# Proiect_v75.net
KiCad netlist of a schematic drawn in EAGLE
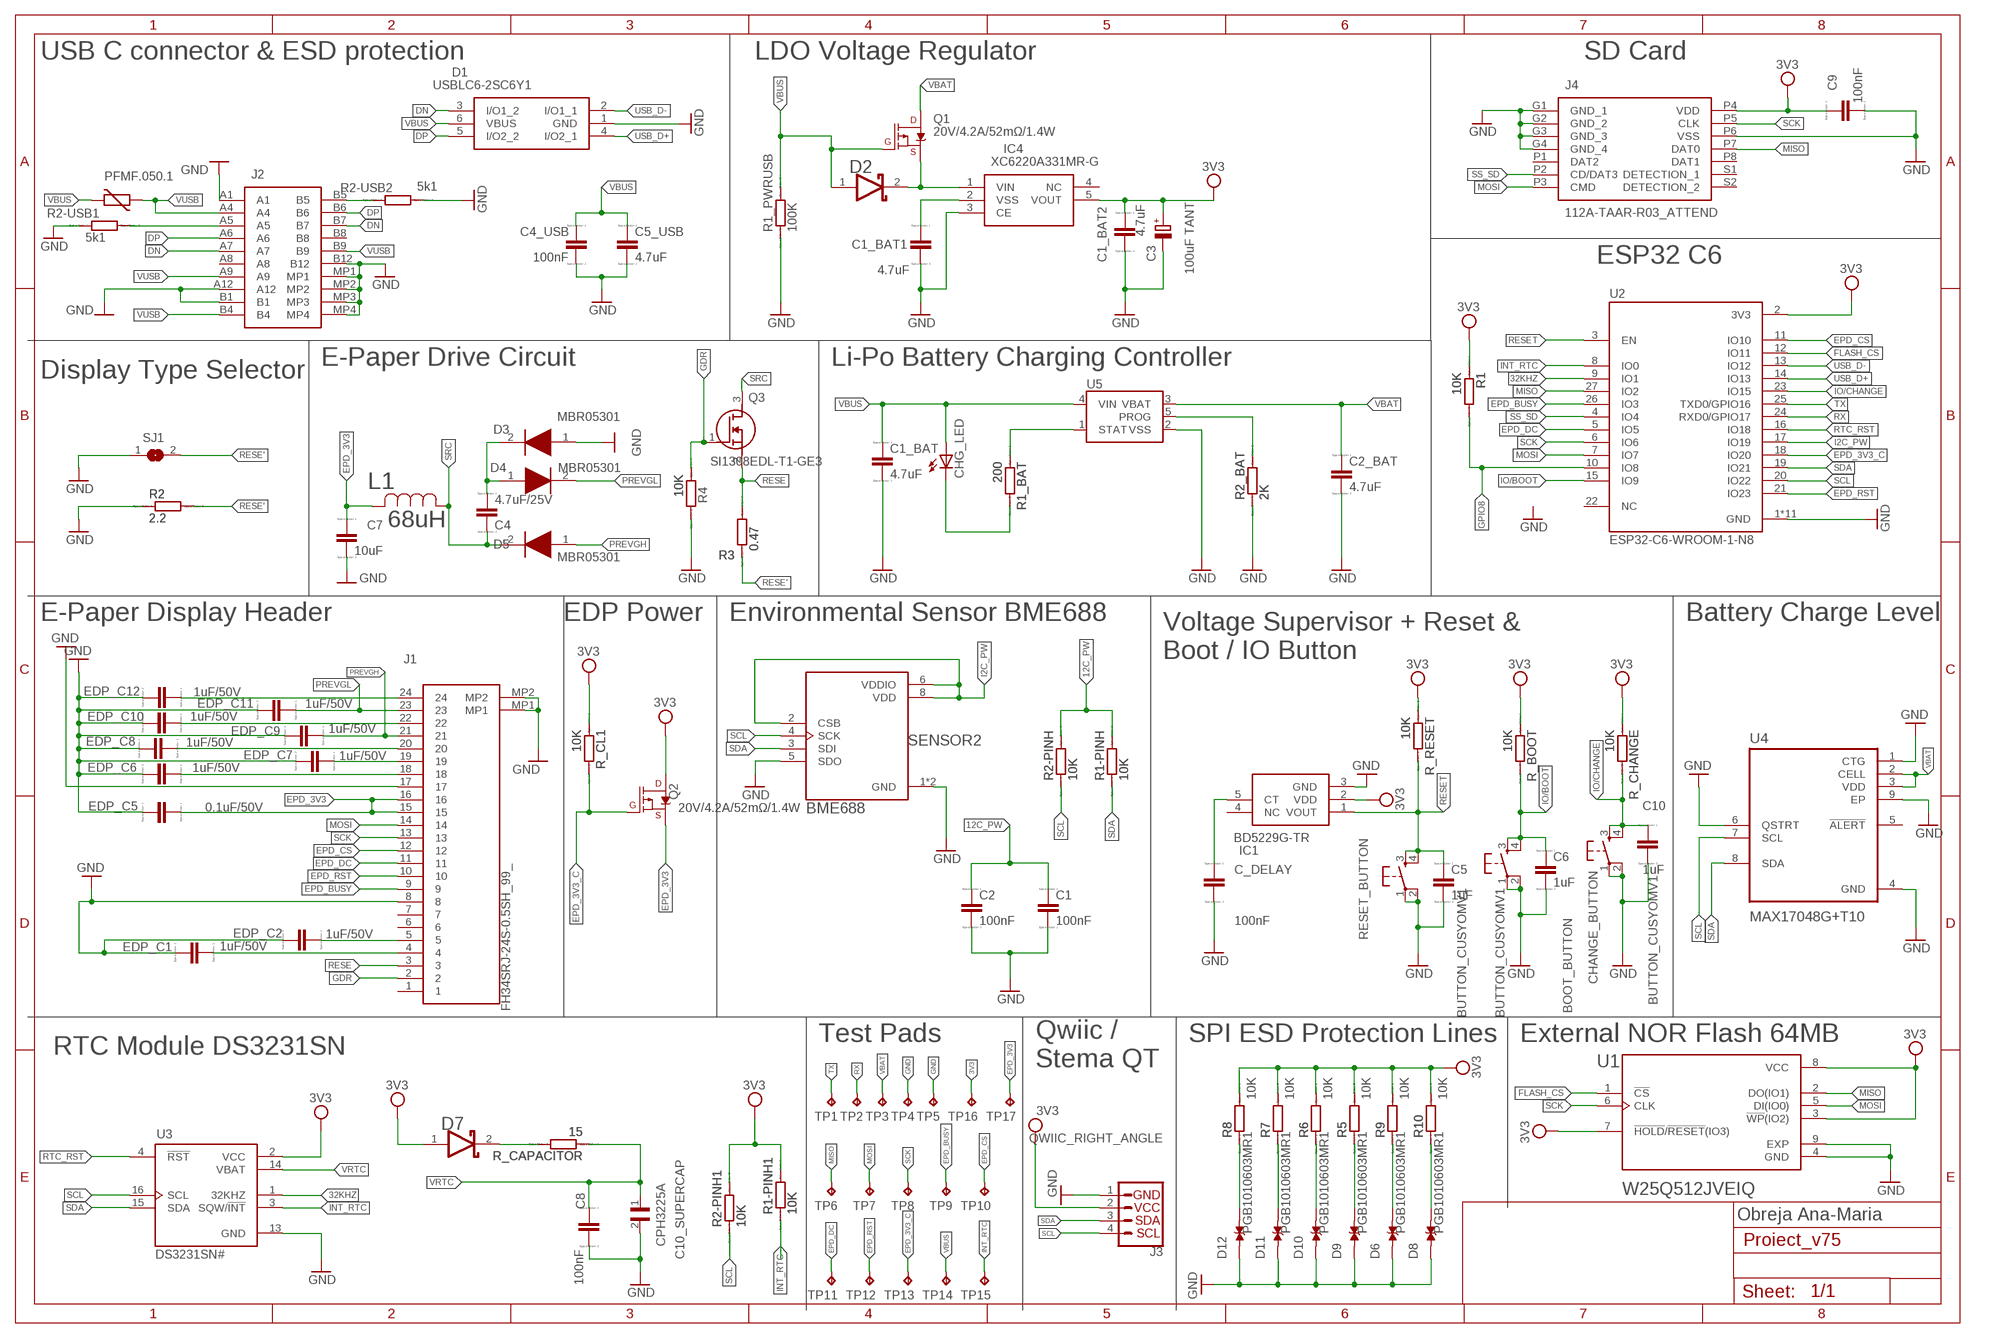
[diagram p0: schematic, sheet 1]

(export (version "E")
  (design (tool "Eeschema 10.0.6"))
  (components
    (comp (ref "BOOT_BUTTON")
      (value "BUTTON_CUSYOMV1")
      (footprint "eagle-import:MYBUTTON")
      (libsource (lib "eagle-import") (part "BUTTON_CUSYOMV1"))
    )
    (comp (ref "C1")
      (value "100nF")
      (footprint "eagle-import:ESP32_WROVER_EAGLE-LTSPICE_C0402")
      (libsource (lib "eagle-import") (part "ESP32_WROVER_EAGLE-LTSPICE_C"))
    )
    (comp (ref "C1_BAT")
      (value "4.7uF")
      (footprint "eagle-import:ESP32_WROVER_EAGLE-LTSPICE_C0402")
      (libsource (lib "eagle-import") (part "ESP32_WROVER_EAGLE-LTSPICE_C"))
    )
    (comp (ref "C1_BAT1")
      (value "4.7uF")
      (footprint "eagle-import:ESP32_WROVER_EAGLE-LTSPICE_C0402")
      (libsource (lib "eagle-import") (part "ESP32_WROVER_EAGLE-LTSPICE_C"))
    )
    (comp (ref "C1_BAT2")
      (value "4.7uF")
      (footprint "eagle-import:ESP32_WROVER_EAGLE-LTSPICE_C0402")
      (libsource (lib "eagle-import") (part "ESP32_WROVER_EAGLE-LTSPICE_C"))
    )
    (comp (ref "C2")
      (value "100nF")
      (footprint "eagle-import:ESP32_WROVER_EAGLE-LTSPICE_C0402")
      (libsource (lib "eagle-import") (part "ESP32_WROVER_EAGLE-LTSPICE_C"))
    )
    (comp (ref "C2_BAT")
      (value "4.7uF")
      (footprint "eagle-import:ESP32_WROVER_EAGLE-LTSPICE_C0402")
      (libsource (lib "eagle-import") (part "ESP32_WROVER_EAGLE-LTSPICE_C"))
    )
    (comp (ref "C3")
      (value "100uF TANT")
      (footprint "eagle-import:RCL_CT3528")
      (libsource (lib "eagle-import") (part "RCL_CPOL-EUCT3528"))
    )
    (comp (ref "C4")
      (value "4.7uF/25V")
      (footprint "eagle-import:ESP32_WROVER_EAGLE-LTSPICE_C0402")
      (libsource (lib "eagle-import") (part "ESP32_WROVER_EAGLE-LTSPICE_C"))
    )
    (comp (ref "C4_USB")
      (value "100nF")
      (footprint "eagle-import:ESP32_WROVER_EAGLE-LTSPICE_C0402")
      (libsource (lib "eagle-import") (part "ESP32_WROVER_EAGLE-LTSPICE_C"))
    )
    (comp (ref "C5")
      (value "1uF")
      (footprint "eagle-import:ESP32_WROVER_EAGLE-LTSPICE_C0402")
      (libsource (lib "eagle-import") (part "ESP32_WROVER_EAGLE-LTSPICE_C"))
    )
    (comp (ref "C5_USB")
      (value "4.7uF")
      (footprint "eagle-import:ESP32_WROVER_EAGLE-LTSPICE_C0402")
      (libsource (lib "eagle-import") (part "ESP32_WROVER_EAGLE-LTSPICE_C"))
    )
    (comp (ref "C6")
      (value "1uF")
      (footprint "eagle-import:ESP32_WROVER_EAGLE-LTSPICE_C0402")
      (libsource (lib "eagle-import") (part "ESP32_WROVER_EAGLE-LTSPICE_C"))
    )
    (comp (ref "C7")
      (value "10uF")
      (footprint "eagle-import:ESP32_WROVER_EAGLE-LTSPICE_C0402")
      (libsource (lib "eagle-import") (part "ESP32_WROVER_EAGLE-LTSPICE_C"))
    )
    (comp (ref "C8")
      (value "100nF")
      (footprint "eagle-import:ESP32_WROVER_EAGLE-LTSPICE_C0402")
      (libsource (lib "eagle-import") (part "ESP32_WROVER_EAGLE-LTSPICE_C"))
    )
    (comp (ref "C9")
      (value "100nF")
      (footprint "eagle-import:ESP32_WROVER_EAGLE-LTSPICE_C0402")
      (libsource (lib "eagle-import") (part "ESP32_WROVER_EAGLE-LTSPICE_C"))
    )
    (comp (ref "C10")
      (value "1uF")
      (footprint "eagle-import:ESP32_WROVER_EAGLE-LTSPICE_C0402")
      (libsource (lib "eagle-import") (part "ESP32_WROVER_EAGLE-LTSPICE_C"))
    )
    (comp (ref "C10_SUPERCAP")
      (value "CPH3225A")
      (footprint "eagle-import:CAPCP3225X100N")
      (fields (field (name "MF") "Seiko Instruments"))
      (libsource (lib "eagle-import") (part "CPH3225A"))
    )
    (comp (ref "CHANGE_BUTTON")
      (value "BUTTON_CUSYOMV1")
      (footprint "eagle-import:MYBUTTON")
      (libsource (lib "eagle-import") (part "BUTTON_CUSYOMV1"))
    )
    (comp (ref "CHG_LED")
      (value "1")
      (footprint "eagle-import:ADAFRUIT_CHIP-LED0603")
      (libsource (lib "eagle-import") (part "ADAFRUIT_LEDCHIP-LED0603"))
    )
    (comp (ref "C_DELAY")
      (value "100nF")
      (footprint "eagle-import:ESP32_WROVER_EAGLE-LTSPICE_C0402")
      (libsource (lib "eagle-import") (part "ESP32_WROVER_EAGLE-LTSPICE_C"))
    )
    (comp (ref "D1")
      (value "USBLC6-2SC6Y1")
      (footprint "eagle-import:SOT95P280X145-6N")
      (libsource (lib "eagle-import") (part "USBLC6-2SC6Y1"))
    )
    (comp (ref "D2")
      (value "ESP32_WROVER_AVX---SD0805S020S1R0_AVX_SD0805S020S1R0_0_0")
      (footprint "eagle-import:ESP32_WROVER_AVX---SD0805S020S1R0_AVX_SD0805S020S1R0_0")
      (libsource (lib "eagle-import") (part "ESP32_WROVER_AVX---SD0805S020S1R0_AVX_SD0805S020S1R0_0_0"))
    )
    (comp (ref "D3")
      (value "MBR05301")
      (footprint "eagle-import:SOD3716X135N")
      (libsource (lib "eagle-import") (part "MBR05301"))
    )
    (comp (ref "D4")
      (value "MBR05301")
      (footprint "eagle-import:SOD3716X135N")
      (libsource (lib "eagle-import") (part "MBR05301"))
    )
    (comp (ref "D5")
      (value "MBR05301")
      (footprint "eagle-import:SOD3716X135N")
      (libsource (lib "eagle-import") (part "MBR05301"))
    )
    (comp (ref "D6")
      (value "PGB1010603MR1")
      (footprint "eagle-import:DIOC1608X36N")
      (libsource (lib "eagle-import") (part "PGB1010603MR1"))
    )
    (comp (ref "D7")
      (value "SD805S020S1R0")
      (footprint "eagle-import:ESP32_WROVER_AVX---SD0805S020S1R0_AVX_SD0805S020S1R0_0")
      (libsource (lib "eagle-import") (part "ESP32_WROVER_AVX---SD0805S020S1R0_AVX_SD0805S020S1R0_0_0"))
    )
    (comp (ref "D8")
      (value "PGB1010603MR1")
      (footprint "eagle-import:DIOC1608X36N")
      (libsource (lib "eagle-import") (part "PGB1010603MR1"))
    )
    (comp (ref "D9")
      (value "PGB1010603MR1")
      (footprint "eagle-import:DIOC1608X36N")
      (libsource (lib "eagle-import") (part "PGB1010603MR1"))
    )
    (comp (ref "D10")
      (value "PGB1010603MR1")
      (footprint "eagle-import:DIOC1608X36N")
      (libsource (lib "eagle-import") (part "PGB1010603MR1"))
    )
    (comp (ref "D11")
      (value "PGB1010603MR1")
      (footprint "eagle-import:DIOC1608X36N")
      (libsource (lib "eagle-import") (part "PGB1010603MR1"))
    )
    (comp (ref "D12")
      (value "PGB1010603MR1")
      (footprint "eagle-import:DIOC1608X36N")
      (libsource (lib "eagle-import") (part "PGB1010603MR1"))
    )
    (comp (ref "EDP_C1")
      (value "1uF/50V")
      (footprint "eagle-import:ESP32_WROVER_EAGLE-LTSPICE_C0402")
      (libsource (lib "eagle-import") (part "ESP32_WROVER_EAGLE-LTSPICE_C"))
    )
    (comp (ref "EDP_C2")
      (value "1uF/50V")
      (footprint "eagle-import:ESP32_WROVER_EAGLE-LTSPICE_C0402")
      (libsource (lib "eagle-import") (part "ESP32_WROVER_EAGLE-LTSPICE_C"))
    )
    (comp (ref "EDP_C5")
      (value "0.1uF/50V")
      (footprint "eagle-import:ESP32_WROVER_EAGLE-LTSPICE_C0402")
      (libsource (lib "eagle-import") (part "ESP32_WROVER_EAGLE-LTSPICE_C"))
    )
    (comp (ref "EDP_C6")
      (value "1uF/50V")
      (footprint "eagle-import:ESP32_WROVER_EAGLE-LTSPICE_C0402")
      (libsource (lib "eagle-import") (part "ESP32_WROVER_EAGLE-LTSPICE_C"))
    )
    (comp (ref "EDP_C7")
      (value "1uF/50V")
      (footprint "eagle-import:ESP32_WROVER_EAGLE-LTSPICE_C0402")
      (libsource (lib "eagle-import") (part "ESP32_WROVER_EAGLE-LTSPICE_C"))
    )
    (comp (ref "EDP_C8")
      (value "1uF/50V")
      (footprint "eagle-import:ESP32_WROVER_EAGLE-LTSPICE_C0402")
      (libsource (lib "eagle-import") (part "ESP32_WROVER_EAGLE-LTSPICE_C"))
    )
    (comp (ref "EDP_C9")
      (value "1uF/50V")
      (footprint "eagle-import:ESP32_WROVER_EAGLE-LTSPICE_C0402")
      (libsource (lib "eagle-import") (part "ESP32_WROVER_EAGLE-LTSPICE_C"))
    )
    (comp (ref "EDP_C10")
      (value "1uF/50V")
      (footprint "eagle-import:ESP32_WROVER_EAGLE-LTSPICE_C0402")
      (libsource (lib "eagle-import") (part "ESP32_WROVER_EAGLE-LTSPICE_C"))
    )
    (comp (ref "EDP_C11")
      (value "1uF/50V")
      (footprint "eagle-import:ESP32_WROVER_EAGLE-LTSPICE_C0402")
      (libsource (lib "eagle-import") (part "ESP32_WROVER_EAGLE-LTSPICE_C"))
    )
    (comp (ref "EDP_C12")
      (value "1uF/50V")
      (footprint "eagle-import:ESP32_WROVER_EAGLE-LTSPICE_C0402")
      (libsource (lib "eagle-import") (part "ESP32_WROVER_EAGLE-LTSPICE_C"))
    )
    (comp (ref "IC1")
      (value "BD5229G-TR")
      (footprint "eagle-import:SOT95P280X125-5N")
      (fields (field (name "MOUSER_PART_NUMBER") "755-BD5229G-TR"))
      (libsource (lib "eagle-import") (part "BD5229G-TR"))
    )
    (comp (ref "IC4")
      (value "XC6220A331MR-G")
      (footprint "eagle-import:SOT95P280X120-5N")
      (fields (field (name "MOUSER_PART_NUMBER") "865-XC6220A331MR-G"))
      (libsource (lib "eagle-import") (part "XC6220A331MR-G"))
    )
    (comp (ref "J1")
      (value "FH34SRJ-24S-0.5SH_99_")
      (footprint "eagle-import:FH34SRJ24S05SH99")
      (fields
        (field (name "MANUFACTURER_PART_NUMBER") "FH34SRJ-24S-0.5SH(99)")
        (field (name "MOUSER_PART_NUMBER") "798-FH34SRJ24S05SH99")
      )
      (libsource (lib "eagle-import") (part "FH34SRJ-24S-0.5SH_99_"))
    )
    (comp (ref "J2")
      (value "SAMACSYS_PARTS_USB4110-GF-A")
      (footprint "eagle-import:SAMACSYS_PARTS_USB4110GFA")
      (fields
        (field (name "MANUFACTURER_PART_NUMBER") "USB4110-GF-A")
        (field (name "MOUSER_PART_NUMBER") "640-USB4110-GF-A")
      )
      (libsource (lib "eagle-import") (part "SAMACSYS_PARTS_USB4110-GF-A"))
    )
    (comp (ref "J3")
      (value "QWIIC_RIGHT_ANGLE")
      (footprint "eagle-import:JST04_1MM_RA")
      (libsource (lib "eagle-import") (part "QWIIC_CONNECTORJS-1MM"))
    )
    (comp (ref "J4")
      (value "112A-TAAR-R03_ATTEND")
      (footprint "eagle-import:112ATAARR03ATTEND")
      (fields (field (name "MANUFACTURER_PART_NUMBER") "112A-TAAR-R03 ATTEND"))
      (libsource (lib "eagle-import") (part "112A-TAAR-R03_ATTEND"))
    )
    (comp (ref "L1")
      (value "68uH")
      (footprint "eagle-import:IND_4828-WE-TPC_WRE")
      (fields
        (field (name "MANUFACTURER_PART_NUMBER") "744043680")
        (field (name "COPYRIGHT") "Copyright (C) 2024 Ultra Librarian. All rights reserved.")
      )
      (libsource (lib "eagle-import") (part "744043680IND_4828-WE-TPC_WRE"))
    )
    (comp (ref "PFMF.050.1")
      (value "ESP32C6_VARISTORCN1812")
      (footprint "eagle-import:ESP32C6_VARISTOR_CT_CN1812")
      (libsource (lib "eagle-import") (part "ESP32C6_VARISTORCN1812"))
    )
    (comp (ref "Q1")
      (value "20V/4.2A/52mΩ/1.4W")
      (footprint "eagle-import:ESP32_WROVER_SPARKFUN-DISCRETESEMI_SOT23-3")
      (libsource (lib "eagle-import") (part "ESP32_WROVER_SPARKFUN-DISCRETESEMI_MOSFET_PCH"))
    )
    (comp (ref "Q2")
      (value "20V/4.2A/52mΩ/1.4W")
      (footprint "eagle-import:ESP32_WROVER_SPARKFUN-DISCRETESEMI_SOT23-3")
      (libsource (lib "eagle-import") (part "ESP32_WROVER_SPARKFUN-DISCRETESEMI_MOSFET_PCH"))
    )
    (comp (ref "Q3")
      (value "SI1308EDL-T1-GE3")
      (footprint "eagle-import:SOT65P210X110-3N")
      (fields (field (name "MF") "Vishay Siliconix"))
      (libsource (lib "eagle-import") (part "SI1308EDL-T1-GE3"))
    )
    (comp (ref "R1")
      (value "10K")
      (footprint "eagle-import:ESP32_WROVER_EAGLE-LTSPICE_R0402")
      (libsource (lib "eagle-import") (part "ESP32_WROVER_EAGLE-LTSPICE_R"))
    )
    (comp (ref "R1-PINH")
      (value "10K")
      (footprint "eagle-import:ESP32_WROVER_EAGLE-LTSPICE_R0402")
      (libsource (lib "eagle-import") (part "ESP32_WROVER_EAGLE-LTSPICE_R"))
    )
    (comp (ref "R1-PINH1")
      (value "10K")
      (footprint "eagle-import:ESP32_WROVER_EAGLE-LTSPICE_R0402")
      (libsource (lib "eagle-import") (part "ESP32_WROVER_EAGLE-LTSPICE_R"))
    )
    (comp (ref "R1_BAT")
      (value "200")
      (footprint "eagle-import:ESP32_WROVER_EAGLE-LTSPICE_R0402")
      (libsource (lib "eagle-import") (part "ESP32_WROVER_EAGLE-LTSPICE_R"))
    )
    (comp (ref "R1_PWRUSB")
      (value "100K")
      (footprint "eagle-import:ESP32_WROVER_EAGLE-LTSPICE_R0402")
      (libsource (lib "eagle-import") (part "ESP32_WROVER_EAGLE-LTSPICE_R"))
    )
    (comp (ref "R2")
      (value "2.2")
      (footprint "eagle-import:ESP32_WROVER_EAGLE-LTSPICE_R0402")
      (libsource (lib "eagle-import") (part "ESP32_WROVER_EAGLE-LTSPICE_R"))
    )
    (comp (ref "R2-PINH")
      (value "10K")
      (footprint "eagle-import:ESP32_WROVER_EAGLE-LTSPICE_R0402")
      (libsource (lib "eagle-import") (part "ESP32_WROVER_EAGLE-LTSPICE_R"))
    )
    (comp (ref "R2-PINH1")
      (value "10K")
      (footprint "eagle-import:ESP32_WROVER_EAGLE-LTSPICE_R0402")
      (libsource (lib "eagle-import") (part "ESP32_WROVER_EAGLE-LTSPICE_R"))
    )
    (comp (ref "R2-USB1")
      (value "5k1")
      (footprint "eagle-import:ESP32_WROVER_EAGLE-LTSPICE_R0402")
      (libsource (lib "eagle-import") (part "ESP32_WROVER_EAGLE-LTSPICE_R"))
    )
    (comp (ref "R2-USB2")
      (value "5k1")
      (footprint "eagle-import:ESP32_WROVER_EAGLE-LTSPICE_R0402")
      (libsource (lib "eagle-import") (part "ESP32_WROVER_EAGLE-LTSPICE_R"))
    )
    (comp (ref "R2_BAT")
      (value "2K")
      (footprint "eagle-import:ESP32_WROVER_EAGLE-LTSPICE_R0402")
      (libsource (lib "eagle-import") (part "ESP32_WROVER_EAGLE-LTSPICE_R"))
    )
    (comp (ref "R3")
      (value "0.47")
      (footprint "eagle-import:ESP32_WROVER_EAGLE-LTSPICE_R0402")
      (libsource (lib "eagle-import") (part "ESP32_WROVER_EAGLE-LTSPICE_R"))
    )
    (comp (ref "R4")
      (value "10K")
      (footprint "eagle-import:ESP32_WROVER_EAGLE-LTSPICE_R0402")
      (libsource (lib "eagle-import") (part "ESP32_WROVER_EAGLE-LTSPICE_R"))
    )
    (comp (ref "R5")
      (value "10K")
      (footprint "eagle-import:ESP32_WROVER_EAGLE-LTSPICE_R0402")
      (libsource (lib "eagle-import") (part "ESP32_WROVER_EAGLE-LTSPICE_R"))
    )
    (comp (ref "R6")
      (value "10K")
      (footprint "eagle-import:ESP32_WROVER_EAGLE-LTSPICE_R0402")
      (libsource (lib "eagle-import") (part "ESP32_WROVER_EAGLE-LTSPICE_R"))
    )
    (comp (ref "R7")
      (value "10K")
      (footprint "eagle-import:ESP32_WROVER_EAGLE-LTSPICE_R0402")
      (libsource (lib "eagle-import") (part "ESP32_WROVER_EAGLE-LTSPICE_R"))
    )
    (comp (ref "R8")
      (value "10K")
      (footprint "eagle-import:ESP32_WROVER_EAGLE-LTSPICE_R0402")
      (libsource (lib "eagle-import") (part "ESP32_WROVER_EAGLE-LTSPICE_R"))
    )
    (comp (ref "R9")
      (value "10K")
      (footprint "eagle-import:ESP32_WROVER_EAGLE-LTSPICE_R0402")
      (libsource (lib "eagle-import") (part "ESP32_WROVER_EAGLE-LTSPICE_R"))
    )
    (comp (ref "R10")
      (value "10K")
      (footprint "eagle-import:ESP32_WROVER_EAGLE-LTSPICE_R0402")
      (libsource (lib "eagle-import") (part "ESP32_WROVER_EAGLE-LTSPICE_R"))
    )
    (comp (ref "RESET_BUTTON")
      (value "BUTTON_CUSYOMV1")
      (footprint "eagle-import:MYBUTTON")
      (libsource (lib "eagle-import") (part "BUTTON_CUSYOMV1"))
    )
    (comp (ref "R_BOOT")
      (value "10K")
      (footprint "eagle-import:ESP32_WROVER_EAGLE-LTSPICE_R0402")
      (libsource (lib "eagle-import") (part "ESP32_WROVER_EAGLE-LTSPICE_R"))
    )
    (comp (ref "R_CAPACITOR")
      (value "15")
      (footprint "eagle-import:ESP32_WROVER_EAGLE-LTSPICE_R0402")
      (libsource (lib "eagle-import") (part "ESP32_WROVER_EAGLE-LTSPICE_R"))
    )
    (comp (ref "R_CHANGE")
      (value "10K")
      (footprint "eagle-import:ESP32_WROVER_EAGLE-LTSPICE_R0402")
      (libsource (lib "eagle-import") (part "ESP32_WROVER_EAGLE-LTSPICE_R"))
    )
    (comp (ref "R_CL1")
      (value "10K")
      (footprint "eagle-import:ESP32_WROVER_EAGLE-LTSPICE_R0402")
      (libsource (lib "eagle-import") (part "ESP32_WROVER_EAGLE-LTSPICE_R"))
    )
    (comp (ref "R_RESET")
      (value "10K")
      (footprint "eagle-import:ESP32_WROVER_EAGLE-LTSPICE_R0402")
      (libsource (lib "eagle-import") (part "ESP32_WROVER_EAGLE-LTSPICE_R"))
    )
    (comp (ref "SENSOR2")
      (value "BME688")
      (footprint "eagle-import:ESP32_WROVER_BME680_PSON80P300X300X100-8N")
      (fields (field (name "MF") "Bosch Sensortec") (field (name "MP") "BME680"))
      (libsource (lib "eagle-import") (part "ESP32_WROVER_BME680_BME680"))
    )
    (comp (ref "SJ1") (value "1") (footprint "eagle-import:SJ") (libsource (lib "eagle-import") (part "SJ")))
    (comp (ref "TP1")
      (value "TP")
      (footprint "eagle-import:TP20R")
      (libsource (lib "eagle-import") (part "TP"))
    )
    (comp (ref "TP2")
      (value "TP")
      (footprint "eagle-import:TP20R")
      (libsource (lib "eagle-import") (part "TP"))
    )
    (comp (ref "TP3")
      (value "TP")
      (footprint "eagle-import:TP20R")
      (libsource (lib "eagle-import") (part "TP"))
    )
    (comp (ref "TP4")
      (value "TP")
      (footprint "eagle-import:TP20R")
      (libsource (lib "eagle-import") (part "TP"))
    )
    (comp (ref "TP5")
      (value "TP")
      (footprint "eagle-import:TP20R")
      (libsource (lib "eagle-import") (part "TP"))
    )
    (comp (ref "TP6")
      (value "TP")
      (footprint "eagle-import:TP20R")
      (libsource (lib "eagle-import") (part "TP"))
    )
    (comp (ref "TP7")
      (value "TP")
      (footprint "eagle-import:TP20R")
      (libsource (lib "eagle-import") (part "TP"))
    )
    (comp (ref "TP8")
      (value "TP")
      (footprint "eagle-import:TP20R")
      (libsource (lib "eagle-import") (part "TP"))
    )
    (comp (ref "TP9")
      (value "TP")
      (footprint "eagle-import:TP20R")
      (libsource (lib "eagle-import") (part "TP"))
    )
    (comp (ref "TP10")
      (value "TP")
      (footprint "eagle-import:TP20R")
      (libsource (lib "eagle-import") (part "TP"))
    )
    (comp (ref "TP11")
      (value "TP")
      (footprint "eagle-import:TP20R")
      (libsource (lib "eagle-import") (part "TP"))
    )
    (comp (ref "TP12")
      (value "TP")
      (footprint "eagle-import:TP20R")
      (libsource (lib "eagle-import") (part "TP"))
    )
    (comp (ref "TP13")
      (value "TP")
      (footprint "eagle-import:TP20R")
      (libsource (lib "eagle-import") (part "TP"))
    )
    (comp (ref "TP14")
      (value "TP")
      (footprint "eagle-import:TP20R")
      (libsource (lib "eagle-import") (part "TP"))
    )
    (comp (ref "TP15")
      (value "TP")
      (footprint "eagle-import:TP20R")
      (libsource (lib "eagle-import") (part "TP"))
    )
    (comp (ref "TP16")
      (value "TP")
      (footprint "eagle-import:TP20R")
      (libsource (lib "eagle-import") (part "TP"))
    )
    (comp (ref "TP17")
      (value "TP")
      (footprint "eagle-import:TP20R")
      (libsource (lib "eagle-import") (part "TP"))
    )
    (comp (ref "U1")
      (value "W25Q512JVEIQ")
      (footprint "eagle-import:SON127P600X800X80-9N")
      (fields (field (name "MF") "Winbond Electronics"))
      (libsource (lib "eagle-import") (part "W25Q512JVEIQ"))
    )
    (comp (ref "U2")
      (value "ESP32-C6-WROOM-1-N8")
      (footprint "eagle-import:XCVR_ESP32-C6-WROOM-1-N8")
      (fields (field (name "MF") "Espressif Systems"))
      (libsource (lib "eagle-import") (part "ESP32-C6-WROOM-1-N8"))
    )
    (comp (ref "U3")
      (value "DS3231SN#")
      (footprint "eagle-import:SOIC127P1032X265-16N")
      (fields (field (name "MF") "Analog Devices"))
      (libsource (lib "eagle-import") (part "DS3231SN#"))
    )
    (comp (ref "U4")
      (value "MAX17048G+T10")
      (footprint "eagle-import:SON50P200X200X80-9N")
      (fields (field (name "MF") "Analog Devices"))
      (libsource (lib "eagle-import") (part "MAX17048G+T10"))
    )
    (comp (ref "U5")
      (value "MCP73831")
      (footprint "eagle-import:ESP32_WROVER_SPARKFUN-IC-POWER_SOT23-5")
      (libsource (lib "eagle-import") (part "ESP32_WROVER_SPARKFUN-IC-POWER_MCP73831"))
    )
  )
  (nets
    (net (code "1") (name "3V3") (class "Default")
      (node (ref "C1_BAT2") (pin "1") (pinfunction "1_1") (pintype "passive"))
      (node (ref "C3") (pin "+") (pinfunction "+_+") (pintype "passive"))
      (node (ref "C9") (pin "1") (pinfunction "1_1") (pintype "passive"))
      (node (ref "D7") (pin "1") (pinfunction "ANODE_1") (pintype "bidirectional"))
      (node (ref "IC1") (pin "2") (pinfunction "VDD_2") (pintype "bidirectional"))
      (node (ref "IC4") (pin "5") (pinfunction "VOUT_5") (pintype "bidirectional"))
      (node (ref "J3") (pin "2") (pinfunction "2_2") (pintype "power_in"))
      (node (ref "J4") (pin "P4") (pinfunction "VDD_P4") (pintype "bidirectional"))
      (node (ref "Q2") (pin "1") (pinfunction "D_1") (pintype "bidirectional"))
      (node (ref "R1") (pin "1") (pinfunction "1_1") (pintype "passive"))
      (node (ref "R1-PINH1") (pin "2") (pinfunction "2_2") (pintype "passive"))
      (node (ref "R10") (pin "2") (pinfunction "2_2") (pintype "passive"))
      (node (ref "R2-PINH1") (pin "2") (pinfunction "2_2") (pintype "passive"))
      (node (ref "R5") (pin "2") (pinfunction "2_2") (pintype "passive"))
      (node (ref "R6") (pin "2") (pinfunction "2_2") (pintype "passive"))
      (node (ref "R7") (pin "2") (pinfunction "2_2") (pintype "passive"))
      (node (ref "R8") (pin "2") (pinfunction "2_2") (pintype "passive"))
      (node (ref "R9") (pin "2") (pinfunction "2_2") (pintype "passive"))
      (node (ref "R_BOOT") (pin "1") (pinfunction "1_1") (pintype "passive"))
      (node (ref "R_CHANGE") (pin "1") (pinfunction "1_1") (pintype "passive"))
      (node (ref "R_CL1") (pin "1") (pinfunction "1_1") (pintype "passive"))
      (node (ref "R_RESET") (pin "1") (pinfunction "1_1") (pintype "passive"))
      (node (ref "TP16") (pin "3V3") (pinfunction "TP_3V3") (pintype "input"))
      (node (ref "U1") (pin "3") (pinfunction "~{WP}(IO2)_3") (pintype "bidirectional"))
      (node (ref "U1") (pin "7") (pinfunction "~{HOLD}/~{RESET}(IO3)_7") (pintype "bidirectional"))
      (node (ref "U1") (pin "8") (pinfunction "VCC_8") (pintype "power_in"))
      (node (ref "U2") (pin "2") (pinfunction "3V3_2") (pintype "power_in"))
      (node (ref "U3") (pin "2") (pinfunction "VCC_2") (pintype "power_in"))
    )
    (net (code "2") (name "12C_PW") (class "Default")
      (node (ref "C1") (pin "1") (pinfunction "1_1") (pintype "passive"))
      (node (ref "C2") (pin "1") (pinfunction "1_1") (pintype "passive"))
      (node (ref "R1-PINH") (pin "2") (pinfunction "2_2") (pintype "passive"))
      (node (ref "R2-PINH") (pin "2") (pinfunction "2_2") (pintype "passive"))
    )
    (net (code "3") (name "32KHZ") (class "Default")
      (node (ref "U2") (pin "9") (pinfunction "IO1_9") (pintype "bidirectional"))
      (node (ref "U3") (pin "1") (pinfunction "32KHZ_1") (pintype "output"))
    )
    (net (code "4") (name "DN") (class "Default")
      (node (ref "D1") (pin "3") (pinfunction "I/O1_2_3") (pintype "bidirectional"))
      (node (ref "J2") (pin "A7") (pinfunction "A7_A7") (pintype "bidirectional"))
      (node (ref "J2") (pin "B7") (pinfunction "B7_B7") (pintype "bidirectional"))
    )
    (net (code "5") (name "DP") (class "Default")
      (node (ref "D1") (pin "5") (pinfunction "I/O2_2_5") (pintype "bidirectional"))
      (node (ref "J2") (pin "A6") (pinfunction "A6_A6") (pintype "bidirectional"))
      (node (ref "J2") (pin "B6") (pinfunction "B6_B6") (pintype "bidirectional"))
    )
    (net (code "6") (name "EPD_3V3") (class "Default")
      (node (ref "C7") (pin "1") (pinfunction "1_1") (pintype "passive"))
      (node (ref "EDP_C5") (pin "1") (pinfunction "1_1") (pintype "passive"))
      (node (ref "J1") (pin "15") (pinfunction "15_15") (pintype "bidirectional"))
      (node (ref "J1") (pin "16") (pinfunction "16_16") (pintype "bidirectional"))
      (node (ref "L1") (pin "2") (pinfunction "2_2") (pintype "passive"))
      (node (ref "Q2") (pin "3") (pinfunction "S_3") (pintype "bidirectional"))
      (node (ref "TP17") (pin "3V3") (pinfunction "TP_3V3") (pintype "input"))
    )
    (net (code "7") (name "EPD_3V3_C") (class "Default")
      (node (ref "Q2") (pin "2") (pinfunction "G_2") (pintype "bidirectional"))
      (node (ref "R_CL1") (pin "2") (pinfunction "2_2") (pintype "passive"))
      (node (ref "TP13") (pin "3V3") (pinfunction "TP_3V3") (pintype "input"))
      (node (ref "U2") (pin "18") (pinfunction "IO20_18") (pintype "bidirectional"))
    )
    (net (code "8") (name "EPD_BUSY") (class "Default")
      (node (ref "J1") (pin "9") (pinfunction "9_9") (pintype "bidirectional"))
      (node (ref "TP9") (pin "3V3") (pinfunction "TP_3V3") (pintype "input"))
      (node (ref "U2") (pin "26") (pinfunction "IO3_26") (pintype "bidirectional"))
    )
    (net (code "9") (name "EPD_CS") (class "Default")
      (node (ref "J1") (pin "12") (pinfunction "12_12") (pintype "bidirectional"))
      (node (ref "TP10") (pin "3V3") (pinfunction "TP_3V3") (pintype "input"))
      (node (ref "U2") (pin "11") (pinfunction "IO10_11") (pintype "bidirectional"))
    )
    (net (code "10") (name "EPD_DC") (class "Default")
      (node (ref "J1") (pin "11") (pinfunction "11_11") (pintype "bidirectional"))
      (node (ref "TP11") (pin "3V3") (pinfunction "TP_3V3") (pintype "input"))
      (node (ref "U2") (pin "5") (pinfunction "IO5_5") (pintype "bidirectional"))
    )
    (net (code "11") (name "EPD_RST") (class "Default")
      (node (ref "J1") (pin "10") (pinfunction "10_10") (pintype "bidirectional"))
      (node (ref "TP12") (pin "3V3") (pinfunction "TP_3V3") (pintype "input"))
      (node (ref "U2") (pin "21") (pinfunction "IO23_21") (pintype "bidirectional"))
    )
    (net (code "12") (name "FLASH_CS") (class "Default")
      (node (ref "U1") (pin "1") (pinfunction "~{CS}_1") (pintype "input"))
      (node (ref "U2") (pin "12") (pinfunction "IO11_12") (pintype "bidirectional"))
    )
    (net (code "13") (name "GDR") (class "Default")
      (node (ref "J1") (pin "2") (pinfunction "2_2") (pintype "bidirectional"))
      (node (ref "Q3") (pin "1") (pinfunction "G_1") (pintype "bidirectional"))
      (node (ref "R4") (pin "1") (pinfunction "1_1") (pintype "passive"))
    )
    (net (code "14") (name "GND") (class "Default")
      (node (ref "BOOT_BUTTON") (pin "1") (pinfunction "1_1") (pintype "passive"))
      (node (ref "BOOT_BUTTON") (pin "2") (pinfunction "2_2") (pintype "passive"))
      (node (ref "C1") (pin "2") (pinfunction "2_2") (pintype "passive"))
      (node (ref "C10") (pin "2") (pinfunction "2_2") (pintype "passive"))
      (node (ref "C10_SUPERCAP") (pin "2") (pinfunction "2_2") (pintype "passive"))
      (node (ref "C1_BAT") (pin "2") (pinfunction "2_2") (pintype "passive"))
      (node (ref "C1_BAT1") (pin "2") (pinfunction "2_2") (pintype "passive"))
      (node (ref "C1_BAT2") (pin "2") (pinfunction "2_2") (pintype "passive"))
      (node (ref "C2") (pin "2") (pinfunction "2_2") (pintype "passive"))
      (node (ref "C2_BAT") (pin "2") (pinfunction "2_2") (pintype "passive"))
      (node (ref "C3") (pin "-") (pinfunction "-_-") (pintype "passive"))
      (node (ref "C4_USB") (pin "2") (pinfunction "2_2") (pintype "passive"))
      (node (ref "C5") (pin "2") (pinfunction "2_2") (pintype "passive"))
      (node (ref "C5_USB") (pin "2") (pinfunction "2_2") (pintype "passive"))
      (node (ref "C6") (pin "2") (pinfunction "2_2") (pintype "passive"))
      (node (ref "C7") (pin "2") (pinfunction "2_2") (pintype "passive"))
      (node (ref "C8") (pin "2") (pinfunction "2_2") (pintype "passive"))
      (node (ref "C9") (pin "2") (pinfunction "2_2") (pintype "passive"))
      (node (ref "CHANGE_BUTTON") (pin "1") (pinfunction "1_1") (pintype "passive"))
      (node (ref "CHANGE_BUTTON") (pin "2") (pinfunction "2_2") (pintype "passive"))
      (node (ref "C_DELAY") (pin "2") (pinfunction "2_2") (pintype "passive"))
      (node (ref "D1") (pin "1") (pinfunction "GND_1") (pintype "bidirectional"))
      (node (ref "D10") (pin "1") (pinfunction "1_1") (pintype "passive"))
      (node (ref "D11") (pin "1") (pinfunction "1_1") (pintype "passive"))
      (node (ref "D12") (pin "1") (pinfunction "1_1") (pintype "passive"))
      (node (ref "D3") (pin "1") (pinfunction "A_1") (pintype "bidirectional"))
      (node (ref "D6") (pin "1") (pinfunction "1_1") (pintype "passive"))
      (node (ref "D8") (pin "1") (pinfunction "1_1") (pintype "passive"))
      (node (ref "D9") (pin "1") (pinfunction "1_1") (pintype "passive"))
      (node (ref "EDP_C1") (pin "2") (pinfunction "2_2") (pintype "passive"))
      (node (ref "EDP_C10") (pin "2") (pinfunction "2_2") (pintype "passive"))
      (node (ref "EDP_C11") (pin "2") (pinfunction "2_2") (pintype "passive"))
      (node (ref "EDP_C12") (pin "2") (pinfunction "2_2") (pintype "passive"))
      (node (ref "EDP_C2") (pin "2") (pinfunction "2_2") (pintype "passive"))
      (node (ref "EDP_C5") (pin "2") (pinfunction "2_2") (pintype "passive"))
      (node (ref "EDP_C6") (pin "2") (pinfunction "2_2") (pintype "passive"))
      (node (ref "EDP_C7") (pin "2") (pinfunction "2_2") (pintype "passive"))
      (node (ref "EDP_C8") (pin "2") (pinfunction "2_2") (pintype "passive"))
      (node (ref "EDP_C9") (pin "2") (pinfunction "2_2") (pintype "passive"))
      (node (ref "IC1") (pin "3") (pinfunction "GND_3") (pintype "bidirectional"))
      (node (ref "IC4") (pin "3") (pinfunction "CE_3") (pintype "bidirectional"))
      (node (ref "J1") (pin "17") (pinfunction "17_17") (pintype "bidirectional"))
      (node (ref "J1") (pin "8") (pinfunction "8_8") (pintype "bidirectional"))
      (node (ref "J1") (pin "MP1") (pinfunction "MP1_MP1") (pintype "bidirectional"))
      (node (ref "J1") (pin "MP2") (pinfunction "MP2_MP2") (pintype "bidirectional"))
      (node (ref "J2") (pin "A1") (pinfunction "A1_A1") (pintype "bidirectional"))
      (node (ref "J2") (pin "A12") (pinfunction "A12_A12") (pintype "bidirectional"))
      (node (ref "J2") (pin "B1") (pinfunction "B1_B1") (pintype "bidirectional"))
      (node (ref "J2") (pin "B12") (pinfunction "B12_B12") (pintype "bidirectional"))
      (node (ref "J2") (pin "MP1") (pinfunction "MP1_MP1") (pintype "bidirectional"))
      (node (ref "J2") (pin "MP2") (pinfunction "MP2_MP2") (pintype "bidirectional"))
      (node (ref "J2") (pin "MP3") (pinfunction "MP3_MP3") (pintype "bidirectional"))
      (node (ref "J2") (pin "MP4") (pinfunction "MP4_MP4") (pintype "bidirectional"))
      (node (ref "J3") (pin "1") (pinfunction "1_1") (pintype "power_in"))
      (node (ref "J4") (pin "G1") (pinfunction "GND_1_G1") (pintype "bidirectional"))
      (node (ref "J4") (pin "G2") (pinfunction "GND_2_G2") (pintype "bidirectional"))
      (node (ref "J4") (pin "G3") (pinfunction "GND_3_G3") (pintype "bidirectional"))
      (node (ref "J4") (pin "G4") (pinfunction "GND_4_G4") (pintype "bidirectional"))
      (node (ref "J4") (pin "P6") (pinfunction "VSS_P6") (pintype "bidirectional"))
      (node (ref "R1_PWRUSB") (pin "1") (pinfunction "1_1") (pintype "passive"))
      (node (ref "R2") (pin "1") (pinfunction "1_1") (pintype "passive"))
      (node (ref "R2-USB1") (pin "1") (pinfunction "1_1") (pintype "passive"))
      (node (ref "R2-USB2") (pin "2") (pinfunction "2_2") (pintype "passive"))
      (node (ref "R2_BAT") (pin "1") (pinfunction "1_1") (pintype "passive"))
      (node (ref "R4") (pin "2") (pinfunction "2_2") (pintype "passive"))
      (node (ref "RESET_BUTTON") (pin "1") (pinfunction "1_1") (pintype "passive"))
      (node (ref "RESET_BUTTON") (pin "2") (pinfunction "2_2") (pintype "passive"))
      (node (ref "SENSOR2") (pin "1") (pinfunction "GND_1") (pintype "power_in"))
      (node (ref "SENSOR2") (pin "5") (pinfunction "SDO_5") (pintype "bidirectional"))
      (node (ref "SENSOR2") (pin "7") (pinfunction "GND_7") (pintype "power_in"))
      (node (ref "SJ1") (pin "1") (pinfunction "1_1") (pintype "passive"))
      (node (ref "TP4") (pin "3V3") (pinfunction "TP_3V3") (pintype "input"))
      (node (ref "TP5") (pin "3V3") (pinfunction "TP_3V3") (pintype "input"))
      (node (ref "U1") (pin "4") (pinfunction "GND_4") (pintype "power_in"))
      (node (ref "U1") (pin "9") (pinfunction "EXP_9") (pintype "passive"))
      (node (ref "U2") (pin "1") (pinfunction "GND_1") (pintype "power_in"))
      (node (ref "U2") (pin "28") (pinfunction "GND_28") (pintype "power_in"))
      (node (ref "U2") (pin "29_1") (pinfunction "GND_29_1") (pintype "power_in"))
      (node (ref "U2") (pin "29_2") (pinfunction "GND_29_2") (pintype "power_in"))
      (node (ref "U2") (pin "29_3") (pinfunction "GND_29_3") (pintype "power_in"))
      (node (ref "U2") (pin "29_4") (pinfunction "GND_29_4") (pintype "power_in"))
      (node (ref "U2") (pin "29_5") (pinfunction "GND_29_5") (pintype "power_in"))
      (node (ref "U2") (pin "29_6") (pinfunction "GND_29_6") (pintype "power_in"))
      (node (ref "U2") (pin "29_7") (pinfunction "GND_29_7") (pintype "power_in"))
      (node (ref "U2") (pin "29_8") (pinfunction "GND_29_8") (pintype "power_in"))
      (node (ref "U2") (pin "29_9") (pinfunction "GND_29_9") (pintype "power_in"))
      (node (ref "U3") (pin "13") (pinfunction "GND_13") (pintype "power_in"))
      (node (ref "U4") (pin "1") (pinfunction "CTG_1") (pintype "power_in"))
      (node (ref "U4") (pin "4") (pinfunction "GND_4") (pintype "power_in"))
      (node (ref "U4") (pin "6") (pinfunction "QSTRT_6") (pintype "input"))
      (node (ref "U4") (pin "9") (pinfunction "EP_9") (pintype "power_in"))
      (node (ref "U5") (pin "2") (pinfunction "VSS_2") (pintype "power_in"))
    )
    (net (code "15") (name "GPIO8") (class "Default")
      (node (ref "R1") (pin "2") (pinfunction "2_2") (pintype "passive"))
      (node (ref "U2") (pin "10") (pinfunction "IO8_10") (pintype "bidirectional"))
    )
    (net (code "16") (name "I2C_PW") (class "Default")
      (node (ref "SENSOR2") (pin "2") (pinfunction "CSB_2") (pintype "input"))
      (node (ref "SENSOR2") (pin "6") (pinfunction "VDDIO_6") (pintype "power_in"))
      (node (ref "SENSOR2") (pin "8") (pinfunction "VDD_8") (pintype "power_in"))
      (node (ref "U2") (pin "17") (pinfunction "IO19_17") (pintype "bidirectional"))
    )
    (net (code "17") (name "INT_RTC") (class "Default")
      (node (ref "R1-PINH1") (pin "1") (pinfunction "1_1") (pintype "passive"))
      (node (ref "TP15") (pin "3V3") (pinfunction "TP_3V3") (pintype "input"))
      (node (ref "U2") (pin "8") (pinfunction "IO0_8") (pintype "bidirectional"))
      (node (ref "U3") (pin "3") (pinfunction "SQW/~{INT}_3") (pintype "output"))
    )
    (net (code "18") (name "IO{slash}BOOT") (class "Default")
      (node (ref "BOOT_BUTTON") (pin "3") (pinfunction "3_3") (pintype "passive"))
      (node (ref "BOOT_BUTTON") (pin "4") (pinfunction "4_4") (pintype "passive"))
      (node (ref "C6") (pin "1") (pinfunction "1_1") (pintype "passive"))
      (node (ref "R_BOOT") (pin "2") (pinfunction "2_2") (pintype "passive"))
      (node (ref "U2") (pin "15") (pinfunction "IO9_15") (pintype "bidirectional"))
    )
    (net (code "19") (name "IO{slash}CHANGE") (class "Default")
      (node (ref "C10") (pin "1") (pinfunction "1_1") (pintype "passive"))
      (node (ref "CHANGE_BUTTON") (pin "3") (pinfunction "3_3") (pintype "passive"))
      (node (ref "CHANGE_BUTTON") (pin "4") (pinfunction "4_4") (pintype "passive"))
      (node (ref "R_CHANGE") (pin "2") (pinfunction "2_2") (pintype "passive"))
      (node (ref "U2") (pin "23") (pinfunction "IO15_23") (pintype "bidirectional"))
    )
    (net (code "20") (name "MISO") (class "Default")
      (node (ref "J4") (pin "P7") (pinfunction "DAT0_P7") (pintype "bidirectional"))
      (node (ref "TP6") (pin "3V3") (pinfunction "TP_3V3") (pintype "input"))
      (node (ref "U1") (pin "2") (pinfunction "DO(IO1)_2") (pintype "bidirectional"))
      (node (ref "U2") (pin "27") (pinfunction "IO2_27") (pintype "bidirectional"))
    )
    (net (code "21") (name "MOSI") (class "Default")
      (node (ref "J1") (pin "14") (pinfunction "14_14") (pintype "bidirectional"))
      (node (ref "J4") (pin "P3") (pinfunction "CMD_P3") (pintype "bidirectional"))
      (node (ref "TP7") (pin "3V3") (pinfunction "TP_3V3") (pintype "input"))
      (node (ref "U1") (pin "5") (pinfunction "DI(IO0)_5") (pintype "bidirectional"))
      (node (ref "U2") (pin "7") (pinfunction "IO7_7") (pintype "bidirectional"))
    )
    (net (code "22") (name "Net-(CHG_LED-PadC)") (class "Default")
      (node (ref "CHG_LED") (pin "C") (pinfunction "C_C") (pintype "passive"))
      (node (ref "R1_BAT") (pin "2") (pinfunction "2_2") (pintype "passive"))
    )
    (net (code "23") (name "Net-(D2-CATHODE)") (class "Default")
      (node (ref "D2") (pin "2") (pinfunction "CATHODE_2") (pintype "bidirectional"))
      (node (ref "IC4") (pin "1") (pinfunction "VIN_1") (pintype "bidirectional"))
      (node (ref "Q1") (pin "3") (pinfunction "S_3") (pintype "bidirectional"))
    )
    (net (code "24") (name "Net-(D3-K)") (class "Default")
      (node (ref "C4") (pin "1") (pinfunction "1_1") (pintype "passive"))
      (node (ref "D3") (pin "2") (pinfunction "K_2") (pintype "bidirectional"))
      (node (ref "D4") (pin "1") (pinfunction "A_1") (pintype "bidirectional"))
    )
    (net (code "25") (name "Net-(D6-Pad2)") (class "Default")
      (node (ref "D6") (pin "2") (pinfunction "2_2") (pintype "passive"))
      (node (ref "R9") (pin "1") (pinfunction "1_1") (pintype "passive"))
    )
    (net (code "26") (name "Net-(D7-CATHODE)") (class "Default")
      (node (ref "D7") (pin "2") (pinfunction "CATHODE_2") (pintype "bidirectional"))
      (node (ref "R_CAPACITOR") (pin "2") (pinfunction "2_2") (pintype "passive"))
    )
    (net (code "27") (name "Net-(D8-Pad2)") (class "Default")
      (node (ref "D8") (pin "2") (pinfunction "2_2") (pintype "passive"))
      (node (ref "R10") (pin "1") (pinfunction "1_1") (pintype "passive"))
    )
    (net (code "28") (name "Net-(D9-Pad2)") (class "Default")
      (node (ref "D9") (pin "2") (pinfunction "2_2") (pintype "passive"))
      (node (ref "R5") (pin "1") (pinfunction "1_1") (pintype "passive"))
    )
    (net (code "29") (name "Net-(D10-Pad2)") (class "Default")
      (node (ref "D10") (pin "2") (pinfunction "2_2") (pintype "passive"))
      (node (ref "R6") (pin "1") (pinfunction "1_1") (pintype "passive"))
    )
    (net (code "30") (name "Net-(D11-Pad2)") (class "Default")
      (node (ref "D11") (pin "2") (pinfunction "2_2") (pintype "passive"))
      (node (ref "R7") (pin "1") (pinfunction "1_1") (pintype "passive"))
    )
    (net (code "31") (name "Net-(D12-Pad2)") (class "Default")
      (node (ref "D12") (pin "2") (pinfunction "2_2") (pintype "passive"))
      (node (ref "R8") (pin "1") (pinfunction "1_1") (pintype "passive"))
    )
    (net (code "32") (name "Net-(EDP_C1-Pad1)") (class "Default")
      (node (ref "EDP_C1") (pin "1") (pinfunction "1_1") (pintype "passive"))
      (node (ref "J1") (pin "4") (pinfunction "4_4") (pintype "bidirectional"))
    )
    (net (code "33") (name "Net-(EDP_C2-Pad1)") (class "Default")
      (node (ref "EDP_C2") (pin "1") (pinfunction "1_1") (pintype "passive"))
      (node (ref "J1") (pin "5") (pinfunction "5_5") (pintype "bidirectional"))
    )
    (net (code "34") (name "Net-(EDP_C6-Pad1)") (class "Default")
      (node (ref "EDP_C6") (pin "1") (pinfunction "1_1") (pintype "passive"))
      (node (ref "J1") (pin "18") (pinfunction "18_18") (pintype "bidirectional"))
    )
    (net (code "35") (name "Net-(EDP_C7-Pad1)") (class "Default")
      (node (ref "EDP_C7") (pin "1") (pinfunction "1_1") (pintype "passive"))
      (node (ref "J1") (pin "19") (pinfunction "19_19") (pintype "bidirectional"))
    )
    (net (code "36") (name "Net-(EDP_C8-Pad1)") (class "Default")
      (node (ref "EDP_C8") (pin "1") (pinfunction "1_1") (pintype "passive"))
      (node (ref "J1") (pin "20") (pinfunction "20_20") (pintype "bidirectional"))
    )
    (net (code "37") (name "Net-(EDP_C10-Pad1)") (class "Default")
      (node (ref "EDP_C10") (pin "1") (pinfunction "1_1") (pintype "passive"))
      (node (ref "J1") (pin "22") (pinfunction "22_22") (pintype "bidirectional"))
    )
    (net (code "38") (name "Net-(EDP_C12-Pad1)") (class "Default")
      (node (ref "EDP_C12") (pin "1") (pinfunction "1_1") (pintype "passive"))
      (node (ref "J1") (pin "24") (pinfunction "24_24") (pintype "bidirectional"))
    )
    (net (code "39") (name "Net-(IC1-CT)") (class "Default")
      (node (ref "C_DELAY") (pin "1") (pinfunction "1_1") (pintype "passive"))
      (node (ref "IC1") (pin "5") (pinfunction "CT_5") (pintype "bidirectional"))
    )
    (net (code "40") (name "Net-(IC4-VSS)") (class "Default")
      (node (ref "C1_BAT1") (pin "1") (pinfunction "1_1") (pintype "passive"))
      (node (ref "IC4") (pin "2") (pinfunction "VSS_2") (pintype "bidirectional"))
    )
    (net (code "41") (name "Net-(J2-PadA5)") (class "Default")
      (node (ref "J2") (pin "A5") (pinfunction "A5_A5") (pintype "bidirectional"))
      (node (ref "R2-USB1") (pin "2") (pinfunction "2_2") (pintype "passive"))
    )
    (net (code "42") (name "Net-(J2-PadB5)") (class "Default")
      (node (ref "J2") (pin "B5") (pinfunction "B5_B5") (pintype "bidirectional"))
      (node (ref "R2-USB2") (pin "1") (pinfunction "1_1") (pintype "passive"))
    )
    (net (code "43") (name "Net-(U5-PROG)") (class "Default")
      (node (ref "R2_BAT") (pin "2") (pinfunction "2_2") (pintype "passive"))
      (node (ref "U5") (pin "5") (pinfunction "PROG_5") (pintype "input"))
    )
    (net (code "44") (name "Net-(U5-STAT)") (class "Default")
      (node (ref "R1_BAT") (pin "1") (pinfunction "1_1") (pintype "passive"))
      (node (ref "U5") (pin "1") (pinfunction "STAT_1") (pintype "output"))
    )
    (net (code "45") (name "PREVGH") (class "Default")
      (node (ref "D5") (pin "1") (pinfunction "A_1") (pintype "bidirectional"))
      (node (ref "EDP_C9") (pin "1") (pinfunction "1_1") (pintype "passive"))
      (node (ref "J1") (pin "21") (pinfunction "21_21") (pintype "bidirectional"))
    )
    (net (code "46") (name "PREVGL") (class "Default")
      (node (ref "D4") (pin "2") (pinfunction "K_2") (pintype "bidirectional"))
      (node (ref "EDP_C11") (pin "1") (pinfunction "1_1") (pintype "passive"))
      (node (ref "J1") (pin "23") (pinfunction "23_23") (pintype "bidirectional"))
    )
    (net (code "47") (name "RESE") (class "Default")
      (node (ref "J1") (pin "3") (pinfunction "3_3") (pintype "bidirectional"))
      (node (ref "Q3") (pin "2") (pinfunction "S_2") (pintype "bidirectional"))
      (node (ref "R3") (pin "2") (pinfunction "2_2") (pintype "passive"))
    )
    (net (code "48") (name "RESE'") (class "Default")
      (node (ref "R2") (pin "2") (pinfunction "2_2") (pintype "passive"))
      (node (ref "R3") (pin "1") (pinfunction "1_1") (pintype "passive"))
      (node (ref "SJ1") (pin "2") (pinfunction "2_2") (pintype "passive"))
    )
    (net (code "49") (name "RESET") (class "Default")
      (node (ref "C5") (pin "1") (pinfunction "1_1") (pintype "passive"))
      (node (ref "IC1") (pin "1") (pinfunction "VOUT_1") (pintype "bidirectional"))
      (node (ref "RESET_BUTTON") (pin "3") (pinfunction "3_3") (pintype "passive"))
      (node (ref "RESET_BUTTON") (pin "4") (pinfunction "4_4") (pintype "passive"))
      (node (ref "R_RESET") (pin "2") (pinfunction "2_2") (pintype "passive"))
      (node (ref "U2") (pin "3") (pinfunction "EN_3") (pintype "input"))
    )
    (net (code "50") (name "RTC_RST") (class "Default")
      (node (ref "U2") (pin "16") (pinfunction "IO18_16") (pintype "bidirectional"))
      (node (ref "U3") (pin "4") (pinfunction "~{RST}_4") (pintype "input"))
    )
    (net (code "51") (name "RX") (class "Default")
      (node (ref "TP2") (pin "3V3") (pinfunction "TP_3V3") (pintype "input"))
      (node (ref "U2") (pin "24") (pinfunction "RXD0/GPIO17_24") (pintype "bidirectional"))
    )
    (net (code "52") (name "SCK") (class "Default")
      (node (ref "J1") (pin "13") (pinfunction "13_13") (pintype "bidirectional"))
      (node (ref "J4") (pin "P5") (pinfunction "CLK_P5") (pintype "bidirectional"))
      (node (ref "TP8") (pin "3V3") (pinfunction "TP_3V3") (pintype "input"))
      (node (ref "U1") (pin "6") (pinfunction "CLK_6") (pintype "input"))
      (node (ref "U2") (pin "6") (pinfunction "IO6_6") (pintype "bidirectional"))
    )
    (net (code "53") (name "SCL") (class "Default")
      (node (ref "J3") (pin "4") (pinfunction "4_4") (pintype "passive"))
      (node (ref "R2-PINH") (pin "1") (pinfunction "1_1") (pintype "passive"))
      (node (ref "R2-PINH1") (pin "1") (pinfunction "1_1") (pintype "passive"))
      (node (ref "SENSOR2") (pin "4") (pinfunction "SCK_4") (pintype "input"))
      (node (ref "U2") (pin "20") (pinfunction "IO22_20") (pintype "bidirectional"))
      (node (ref "U3") (pin "16") (pinfunction "SCL_16") (pintype "input"))
      (node (ref "U4") (pin "7") (pinfunction "SCL_7") (pintype "input"))
    )
    (net (code "54") (name "SDA") (class "Default")
      (node (ref "J3") (pin "3") (pinfunction "3_3") (pintype "passive"))
      (node (ref "R1-PINH") (pin "1") (pinfunction "1_1") (pintype "passive"))
      (node (ref "SENSOR2") (pin "3") (pinfunction "SDI_3") (pintype "bidirectional"))
      (node (ref "U2") (pin "19") (pinfunction "IO21_19") (pintype "bidirectional"))
      (node (ref "U3") (pin "15") (pinfunction "SDA_15") (pintype "bidirectional"))
      (node (ref "U4") (pin "8") (pinfunction "SDA_8") (pintype "bidirectional"))
    )
    (net (code "55") (name "SRC") (class "Default")
      (node (ref "C4") (pin "2") (pinfunction "2_2") (pintype "passive"))
      (node (ref "D5") (pin "2") (pinfunction "K_2") (pintype "bidirectional"))
      (node (ref "L1") (pin "1") (pinfunction "1_1") (pintype "passive"))
      (node (ref "Q3") (pin "3") (pinfunction "D_3") (pintype "bidirectional"))
    )
    (net (code "56") (name "SS_SD") (class "Default")
      (node (ref "J4") (pin "P2") (pinfunction "CD/DAT3_P2") (pintype "bidirectional"))
      (node (ref "U2") (pin "4") (pinfunction "IO4_4") (pintype "bidirectional"))
    )
    (net (code "57") (name "TX") (class "Default")
      (node (ref "TP1") (pin "3V3") (pinfunction "TP_3V3") (pintype "input"))
      (node (ref "U2") (pin "25") (pinfunction "TXD0/GPIO16_25") (pintype "bidirectional"))
    )
    (net (code "58") (name "USB_D+") (class "Default")
      (node (ref "D1") (pin "4") (pinfunction "I/O2_1_4") (pintype "bidirectional"))
      (node (ref "U2") (pin "14") (pinfunction "IO13_14") (pintype "bidirectional"))
    )
    (net (code "59") (name "USB_D-") (class "Default")
      (node (ref "D1") (pin "2") (pinfunction "I/O1_1_2") (pintype "bidirectional"))
      (node (ref "U2") (pin "13") (pinfunction "IO12_13") (pintype "bidirectional"))
    )
    (net (code "60") (name "VBAT") (class "Default")
      (node (ref "C2_BAT") (pin "1") (pinfunction "1_1") (pintype "passive"))
      (node (ref "Q1") (pin "1") (pinfunction "D_1") (pintype "bidirectional"))
      (node (ref "TP3") (pin "3V3") (pinfunction "TP_3V3") (pintype "input"))
      (node (ref "U4") (pin "2") (pinfunction "CELL_2") (pintype "power_in"))
      (node (ref "U4") (pin "3") (pinfunction "VDD_3") (pintype "power_in"))
      (node (ref "U5") (pin "3") (pinfunction "VBAT_3") (pintype "power_in"))
    )
    (net (code "61") (name "VBUS") (class "Default")
      (node (ref "C1_BAT") (pin "1") (pinfunction "1_1") (pintype "passive"))
      (node (ref "C4_USB") (pin "1") (pinfunction "1_1") (pintype "passive"))
      (node (ref "C5_USB") (pin "1") (pinfunction "1_1") (pintype "passive"))
      (node (ref "CHG_LED") (pin "A") (pinfunction "A_A") (pintype "passive"))
      (node (ref "D1") (pin "6") (pinfunction "VBUS_6") (pintype "bidirectional"))
      (node (ref "D2") (pin "1") (pinfunction "ANODE_1") (pintype "bidirectional"))
      (node (ref "PFMF.050.1") (pin "2") (pinfunction "2_2") (pintype "passive"))
      (node (ref "Q1") (pin "2") (pinfunction "G_2") (pintype "bidirectional"))
      (node (ref "R1_PWRUSB") (pin "2") (pinfunction "2_2") (pintype "passive"))
      (node (ref "TP14") (pin "3V3") (pinfunction "TP_3V3") (pintype "input"))
      (node (ref "U5") (pin "4") (pinfunction "VIN_4") (pintype "power_in"))
    )
    (net (code "62") (name "VRTC") (class "Default")
      (node (ref "C10_SUPERCAP") (pin "1") (pinfunction "1_1") (pintype "passive"))
      (node (ref "C8") (pin "1") (pinfunction "1_1") (pintype "passive"))
      (node (ref "R_CAPACITOR") (pin "1") (pinfunction "1_1") (pintype "passive"))
      (node (ref "U3") (pin "14") (pinfunction "VBAT_14") (pintype "power_in"))
    )
    (net (code "63") (name "VUSB") (class "Default")
      (node (ref "J2") (pin "A4") (pinfunction "A4_A4") (pintype "bidirectional"))
      (node (ref "J2") (pin "A9") (pinfunction "A9_A9") (pintype "bidirectional"))
      (node (ref "J2") (pin "B4") (pinfunction "B4_B4") (pintype "bidirectional"))
      (node (ref "J2") (pin "B9") (pinfunction "B9_B9") (pintype "bidirectional"))
      (node (ref "PFMF.050.1") (pin "1") (pinfunction "1_1") (pintype "passive"))
    )
    (net (code "64") (name "unconnected-(IC1-NC-Pad4)") (class "Default")
      (node (ref "IC1") (pin "4") (pinfunction "NC_4") (pintype "no_connect"))
    )
    (net (code "65") (name "unconnected-(IC4-NC-Pad4)") (class "Default")
      (node (ref "IC4") (pin "4") (pinfunction "NC_4") (pintype "no_connect"))
    )
    (net (code "66") (name "unconnected-(J1-Pad1)") (class "Default")
      (node (ref "J1") (pin "1") (pinfunction "1_1") (pintype "bidirectional"))
    )
    (net (code "67") (name "unconnected-(J1-Pad6)") (class "Default")
      (node (ref "J1") (pin "6") (pinfunction "6_6") (pintype "bidirectional"))
    )
    (net (code "68") (name "unconnected-(J1-Pad7)") (class "Default")
      (node (ref "J1") (pin "7") (pinfunction "7_7") (pintype "bidirectional"))
    )
    (net (code "69") (name "unconnected-(J2-PadA8)") (class "Default")
      (node (ref "J2") (pin "A8") (pinfunction "A8_A8") (pintype "bidirectional"))
    )
    (net (code "70") (name "unconnected-(J2-PadB8)") (class "Default")
      (node (ref "J2") (pin "B8") (pinfunction "B8_B8") (pintype "bidirectional"))
    )
    (net (code "71") (name "unconnected-(J4-DAT1-PadP8)") (class "Default")
      (node (ref "J4") (pin "P8") (pinfunction "DAT1_P8") (pintype "bidirectional"))
    )
    (net (code "72") (name "unconnected-(J4-DAT2-PadP1)") (class "Default")
      (node (ref "J4") (pin "P1") (pinfunction "DAT2_P1") (pintype "bidirectional"))
    )
    (net (code "73") (name "unconnected-(J4-DETECTION_1-PadS1)") (class "Default")
      (node (ref "J4") (pin "S1") (pinfunction "DETECTION_1_S1") (pintype "bidirectional"))
    )
    (net (code "74") (name "unconnected-(J4-DETECTION_2-PadS2)") (class "Default")
      (node (ref "J4") (pin "S2") (pinfunction "DETECTION_2_S2") (pintype "bidirectional"))
    )
    (net (code "75") (name "unconnected-(U2-NC-Pad22)") (class "Default")
      (node (ref "U2") (pin "22") (pinfunction "NC_22") (pintype "no_connect"))
    )
    (net (code "76") (name "unconnected-(U4-~{ALERT}-Pad5)") (class "Default")
      (node (ref "U4") (pin "5") (pinfunction "~{ALERT}_5") (pintype "output"))
    )
  )
)
